# TheStaticTurtle_oshw-sdi3g-fiber__schema.net
KiCad netlist of a schematic drawn in Altium Designer
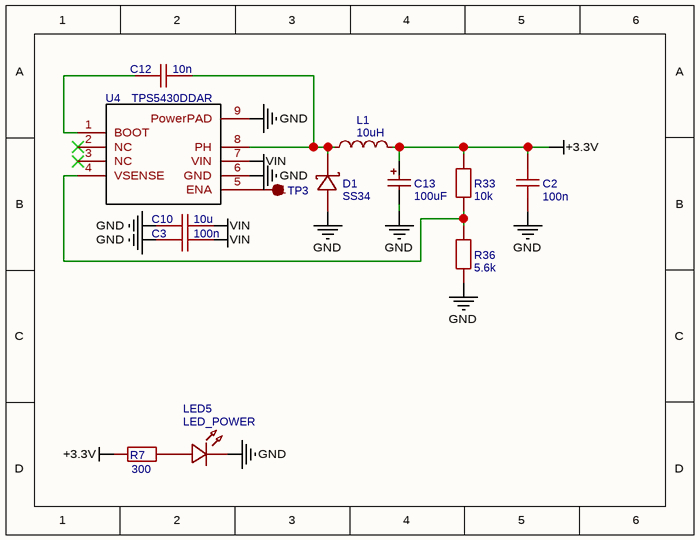
[diagram p0: TheStaticTurtle_oshw-sdi3g-fiber__schematic_V4-Normal_OSHW_BiDi_SDI_Fiber_Converter_V4_Normal_2024-11-17__Power.schdoc]

(export (version "E")
  (design (tool "Eeschema 10.0.6"))
  (components
    (comp (ref "C2")
      (value "100n")
      (fields (field (name "CONTRIBUTOR") "LCEDA_Lib"))
      (libsource (lib "altium-import") (part "root_1_100n_"))
    )
    (comp (ref "C3")
      (value "100n")
      (fields (field (name "CONTRIBUTOR") "LCEDA_Lib"))
      (libsource (lib "altium-import") (part "root_0_100n_"))
    )
    (comp (ref "C10")
      (value "10u")
      (fields (field (name "CONTRIBUTOR") "LCEDA_Lib"))
      (libsource (lib "altium-import") (part "root_0_10u_"))
    )
    (comp (ref "C12")
      (value "10n")
      (fields (field (name "CONTRIBUTOR") "LCEDA_Lib"))
      (libsource (lib "altium-import") (part "root_0_10n_"))
    )
    (comp (ref "C13")
      (value "100uF")
      (fields (field (name "MANUFACTURER") "Kyocera AVX") (field (name "MANUFACTURER PART") "TAJB107K006RNJ"))
      (libsource (lib "altium-import") (part "root_1_100uF_"))
    )
    (comp (ref "D1")
      (value "SS34")
      (fields (field (name "MANUFACTURER") "MDD(辰达半导体)"))
      (libsource (lib "altium-import") (part "root_3_SS34_"))
    )
    (comp (ref "L1")
      (value "10uH")
      (fields (field (name "MANUFACTURER") "Sunlord(顺络)") (field (name "MANUFACTURER PART") "SWPA4030S100MT"))
      (libsource (lib "altium-import") (part "root_0_10uH_"))
    )
    (comp (ref "LED5")
      (value "LED_POWER")
      (fields
        (field (name "MANUFACTURER") "方舟 ARKLED")
        (field (name "MANUFACTURER PART") "D-B080508B1-KS2")
        (field (name "CONTRIBUTOR") "LCEDA_Lib")
      )
      (libsource (lib "altium-import") (part "root_0_LED_POWER_"))
    )
    (comp (ref "R7")
      (value "300")
      (fields (field (name "CONTRIBUTOR") "LCEDA_Lib"))
      (libsource (lib "altium-import") (part "root_2_300_"))
    )
    (comp (ref "R33")
      (value "10k")
      (fields (field (name "CONTRIBUTOR") "LCEDA_Lib"))
      (libsource (lib "altium-import") (part "root_3_10k_"))
    )
    (comp (ref "R36")
      (value "5.6k")
      (fields (field (name "CONTRIBUTOR") "LCEDA_Lib"))
      (libsource (lib "altium-import") (part "root_3_5.6k_"))
    )
    (comp (ref "TP3")
      (value "TEST-POINT-PTH-1X1")
      (libsource (lib "altium-import") (part "root_2_TEST-POINT-PTH-1X1_"))
    )
    (comp (ref "U4")
      (value "TPS5430DDAR")
      (fields (field (name "MANUFACTURER") "TI(德州仪器)"))
      (libsource (lib "altium-import") (part "root_0_TPS5430DDAR_"))
    )
  )
  (nets
    (net (code "1") (name "+3.3V") (class "Default")
      (node (ref "C13") (pin "1") (pinfunction "1_1") (pintype "passive"))
      (node (ref "C2") (pin "2") (pinfunction "2_2") (pintype "passive"))
      (node (ref "L1") (pin "2") (pinfunction "2_2") (pintype "passive"))
      (node (ref "R33") (pin "1") (pinfunction "1_1") (pintype "passive"))
      (node (ref "R7") (pin "2") (pinfunction "2_2") (pintype "passive"))
    )
    (net (code "2") (name "GND") (class "Default")
      (node (ref "C10") (pin "1") (pinfunction "1_1") (pintype "passive"))
      (node (ref "C13") (pin "2") (pinfunction "2_2") (pintype "passive"))
      (node (ref "C2") (pin "1") (pinfunction "1_1") (pintype "passive"))
      (node (ref "C3") (pin "1") (pinfunction "1_1") (pintype "passive"))
      (node (ref "D1") (pin "2") (pinfunction "A_2") (pintype "passive"))
      (node (ref "LED5") (pin "2") (pinfunction "2_2") (pintype "passive"))
      (node (ref "R36") (pin "2") (pinfunction "2_2") (pintype "passive"))
      (node (ref "U4") (pin "6") (pinfunction "GND_6") (pintype "passive"))
      (node (ref "U4") (pin "9") (pinfunction "PowerPAD_9") (pintype "passive"))
    )
    (net (code "3") (name "Net-(D1-K)") (class "Default")
      (node (ref "C12") (pin "2") (pinfunction "2_2") (pintype "passive"))
      (node (ref "D1") (pin "1") (pinfunction "K_1") (pintype "passive"))
      (node (ref "L1") (pin "1") (pinfunction "1_1") (pintype "passive"))
      (node (ref "U4") (pin "8") (pinfunction "PH_8") (pintype "passive"))
    )
    (net (code "4") (name "Net-(LED5-Pad1)") (class "Default")
      (node (ref "LED5") (pin "1") (pinfunction "1_1") (pintype "passive"))
      (node (ref "R7") (pin "1") (pinfunction "1_1") (pintype "passive"))
    )
    (net (code "5") (name "Net-(U4-BOOT)") (class "Default")
      (node (ref "C12") (pin "1") (pinfunction "1_1") (pintype "passive"))
      (node (ref "U4") (pin "1") (pinfunction "BOOT_1") (pintype "passive"))
    )
    (net (code "6") (name "Net-(U4-ENA)") (class "Default")
      (node (ref "TP3") (pin "1") (pinfunction "1_1") (pintype "passive"))
      (node (ref "U4") (pin "5") (pinfunction "ENA_5") (pintype "passive"))
    )
    (net (code "7") (name "Net-(U4-VSENSE)") (class "Default")
      (node (ref "R33") (pin "2") (pinfunction "2_2") (pintype "passive"))
      (node (ref "R36") (pin "1") (pinfunction "1_1") (pintype "passive"))
      (node (ref "U4") (pin "4") (pinfunction "VSENSE_4") (pintype "passive"))
    )
    (net (code "8") (name "VIN") (class "Default")
      (node (ref "C10") (pin "2") (pinfunction "2_2") (pintype "passive"))
      (node (ref "C3") (pin "2") (pinfunction "2_2") (pintype "passive"))
      (node (ref "U4") (pin "7") (pinfunction "VIN_7") (pintype "passive"))
    )
    (net (code "9") (name "unconnected-(U4-NC-Pad2)") (class "Default")
      (node (ref "U4") (pin "2") (pinfunction "NC_2") (pintype "passive+no_connect"))
    )
    (net (code "10") (name "unconnected-(U4-NC-Pad3)") (class "Default")
      (node (ref "U4") (pin "3") (pinfunction "NC_3") (pintype "passive+no_connect"))
    )
  )
)
